# DIGISPARK_PRODUCTION_REV3.net
KiCad netlist of a schematic drawn in EAGLE
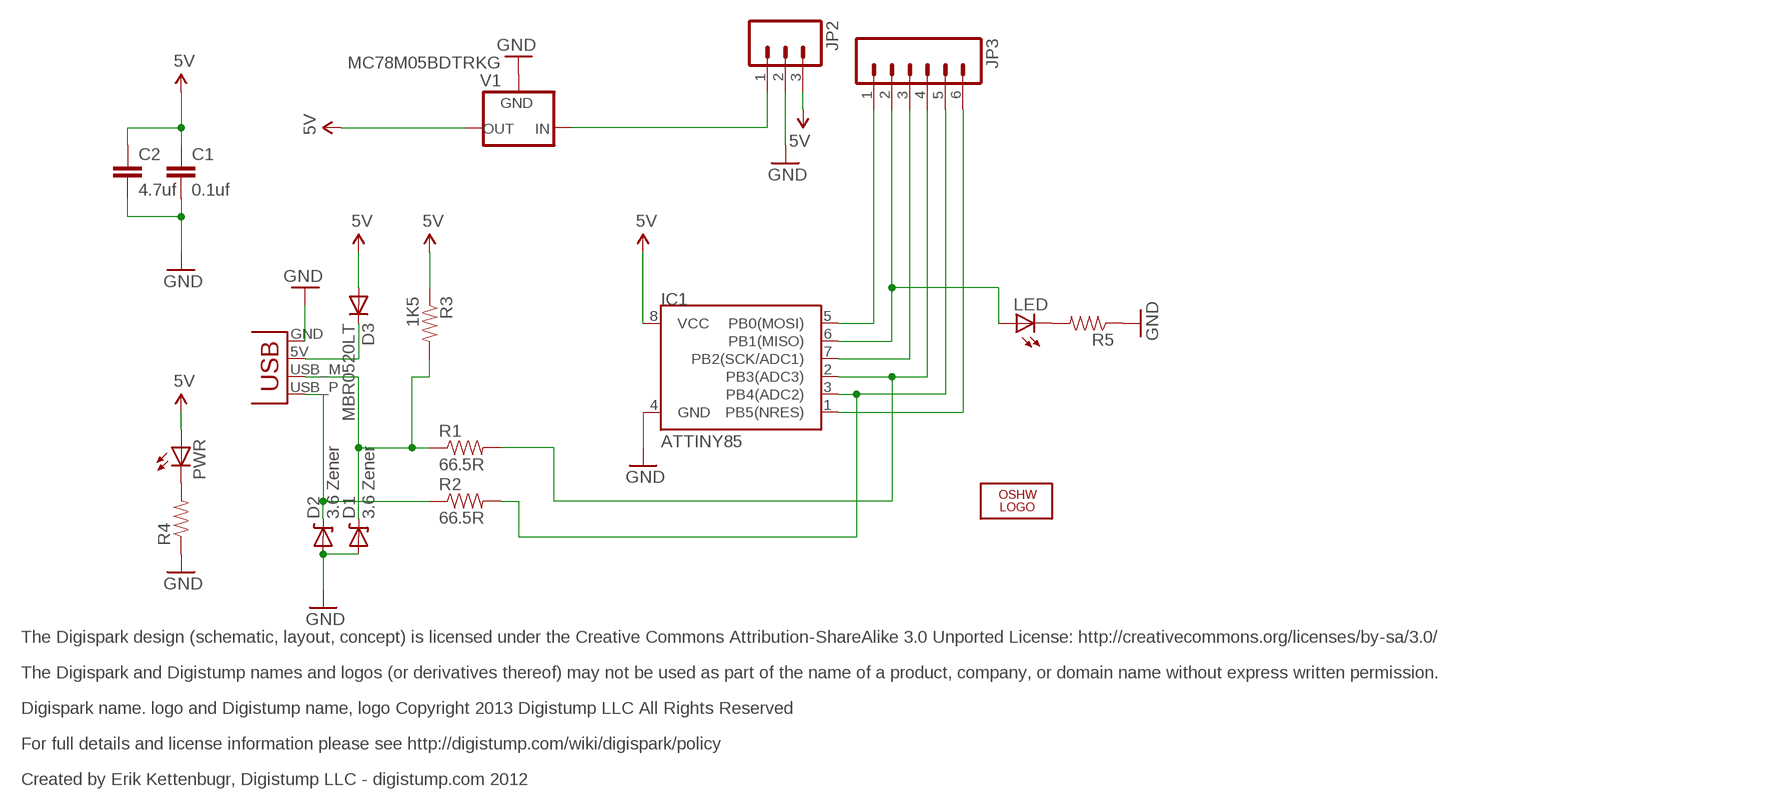
[diagram p0: schematic, sheet 1]

(export (version "E")
  (design (tool "Eeschema 10.0.6"))
  (components
    (comp (ref "C1")
      (value "0.1uf")
      (footprint "eagle-import:0402-CAP")
      (libsource (lib "eagle-import") (part "CAP0402-CAP"))
    )
    (comp (ref "C2")
      (value "4.7uf")
      (footprint "eagle-import:0805")
      (libsource (lib "eagle-import") (part "CAP0805"))
    )
    (comp (ref "D1")
      (value "3.6 Zener")
      (footprint "eagle-import:SOD-323")
      (libsource (lib "eagle-import") (part "DIODE-ZENER-BZT52"))
    )
    (comp (ref "D2")
      (value "3.6 Zener")
      (footprint "eagle-import:SOD-323")
      (libsource (lib "eagle-import") (part "DIODE-ZENER-BZT52"))
    )
    (comp (ref "D3")
      (value "MBR0520LT")
      (footprint "eagle-import:SOD123")
      (libsource (lib "eagle-import") (part "MBR0520LT"))
    )
    (comp (ref "IC1")
      (value "ATTINY85")
      (footprint "eagle-import:SO08-EIAJ")
      (libsource (lib "eagle-import") (part "ATTINY45"))
    )
    (comp (ref "JP2")
      (value "M03PTH")
      (footprint "eagle-import:1X03")
      (libsource (lib "eagle-import") (part "M03PTH"))
    )
    (comp (ref "JP3")
      (value "M06SIP")
      (footprint "eagle-import:1X06")
      (libsource (lib "eagle-import") (part "M06SIP"))
    )
    (comp (ref "LED")
      (value "LED0603")
      (footprint "eagle-import:LED-0603")
      (libsource (lib "eagle-import") (part "LED0603"))
    )
    (comp (ref "LOGO2")
      (value "LOGO-OSHW-10MILX0200-NT")
      (footprint "eagle-import:OSHW_10X200_NOTEXT")
      (libsource (lib "eagle-import") (part "LOGO-OSHW-10MILX0200-NT"))
    )
    (comp (ref "PWR")
      (value "LED0603")
      (footprint "eagle-import:LED-0603")
      (libsource (lib "eagle-import") (part "LED0603"))
    )
    (comp (ref "R1")
      (value "66.5R")
      (footprint "eagle-import:0402-RES")
      (libsource (lib "eagle-import") (part "RESISTOR0402-RES"))
    )
    (comp (ref "R2")
      (value "66.5R")
      (footprint "eagle-import:0402-RES")
      (libsource (lib "eagle-import") (part "RESISTOR0402-RES"))
    )
    (comp (ref "R3")
      (value "1K5")
      (footprint "eagle-import:0402-RES")
      (libsource (lib "eagle-import") (part "RESISTOR0402-RES"))
    )
    (comp (ref "R4")
      (value "RESISTOR0402-RES")
      (footprint "eagle-import:0402-RES")
      (libsource (lib "eagle-import") (part "RESISTOR0402-RES"))
    )
    (comp (ref "R5")
      (value "RESISTOR0402-RES")
      (footprint "eagle-import:0402-RES")
      (libsource (lib "eagle-import") (part "RESISTOR0402-RES"))
    )
    (comp (ref "V1")
      (value "MC78M05BDTRKG")
      (footprint "eagle-import:DPACK")
      (libsource (lib "eagle-import") (part "LP2950?CDT-3.0"))
    )
    (comp (ref "X1")
      (value "USBPCB")
      (footprint "eagle-import:USB-A-PCB")
      (libsource (lib "eagle-import") (part "USBPCB"))
    )
  )
  (nets
    (net (code "1") (name "5V") (class "Default")
      (node (ref "C1") (pin "1") (pinfunction "1_1") (pintype "passive"))
      (node (ref "C2") (pin "1") (pinfunction "1_1") (pintype "passive"))
      (node (ref "D3") (pin "A") (pinfunction "A_A") (pintype "passive"))
      (node (ref "IC1") (pin "8") (pinfunction "VCC_8") (pintype "bidirectional"))
      (node (ref "JP2") (pin "3") (pinfunction "3_3") (pintype "passive"))
      (node (ref "PWR") (pin "A") (pinfunction "A_A") (pintype "passive"))
      (node (ref "R3") (pin "1") (pinfunction "1_1") (pintype "passive"))
      (node (ref "V1") (pin "3") (pinfunction "OUT_3") (pintype "passive"))
    )
    (net (code "2") (name "GND") (class "Default")
      (node (ref "C1") (pin "2") (pinfunction "2_2") (pintype "passive"))
      (node (ref "C2") (pin "2") (pinfunction "2_2") (pintype "passive"))
      (node (ref "D1") (pin "2") (pinfunction "A_2") (pintype "passive"))
      (node (ref "D2") (pin "2") (pinfunction "A_2") (pintype "passive"))
      (node (ref "IC1") (pin "4") (pinfunction "GND_4") (pintype "bidirectional"))
      (node (ref "JP2") (pin "2") (pinfunction "2_2") (pintype "passive"))
      (node (ref "R4") (pin "1") (pinfunction "1_1") (pintype "passive"))
      (node (ref "R5") (pin "1") (pinfunction "1_1") (pintype "passive"))
      (node (ref "V1") (pin "4") (pinfunction "GND_4") (pintype "input"))
      (node (ref "X1") (pin "GND") (pinfunction "GND_GND") (pintype "bidirectional"))
    )
    (net (code "3") (name "Net-(D1-C)") (class "Default")
      (node (ref "D1") (pin "1") (pinfunction "C_1") (pintype "passive"))
      (node (ref "R1") (pin "1") (pinfunction "1_1") (pintype "passive"))
      (node (ref "R3") (pin "2") (pinfunction "2_2") (pintype "passive"))
      (node (ref "X1") (pin "USB_M") (pinfunction "D-_USB_M") (pintype "bidirectional"))
    )
    (net (code "4") (name "Net-(D2-C)") (class "Default")
      (node (ref "D2") (pin "1") (pinfunction "C_1") (pintype "passive"))
      (node (ref "R2") (pin "1") (pinfunction "1_1") (pintype "passive"))
      (node (ref "X1") (pin "USB_P") (pinfunction "D+_USB_P") (pintype "bidirectional"))
    )
    (net (code "5") (name "Net-(IC1-PB0(MOSI))") (class "Default")
      (node (ref "IC1") (pin "5") (pinfunction "PB0(MOSI)_5") (pintype "bidirectional"))
      (node (ref "JP3") (pin "1") (pinfunction "1_1") (pintype "passive"))
    )
    (net (code "6") (name "Net-(IC1-PB1(MISO))") (class "Default")
      (node (ref "IC1") (pin "6") (pinfunction "PB1(MISO)_6") (pintype "bidirectional"))
      (node (ref "JP3") (pin "2") (pinfunction "2_2") (pintype "passive"))
      (node (ref "LED") (pin "A") (pinfunction "A_A") (pintype "passive"))
    )
    (net (code "7") (name "Net-(IC1-PB2(SCK{slash}ADC1))") (class "Default")
      (node (ref "IC1") (pin "7") (pinfunction "PB2(SCK/ADC1)_7") (pintype "bidirectional"))
      (node (ref "JP3") (pin "3") (pinfunction "3_3") (pintype "passive"))
    )
    (net (code "8") (name "Net-(IC1-PB3(ADC3))") (class "Default")
      (node (ref "IC1") (pin "2") (pinfunction "PB3(ADC3)_2") (pintype "bidirectional"))
      (node (ref "JP3") (pin "4") (pinfunction "4_4") (pintype "passive"))
      (node (ref "R1") (pin "2") (pinfunction "2_2") (pintype "passive"))
    )
    (net (code "9") (name "Net-(IC1-PB4(ADC2))") (class "Default")
      (node (ref "IC1") (pin "3") (pinfunction "PB4(ADC2)_3") (pintype "bidirectional"))
      (node (ref "JP3") (pin "5") (pinfunction "5_5") (pintype "passive"))
      (node (ref "R2") (pin "2") (pinfunction "2_2") (pintype "passive"))
    )
    (net (code "10") (name "Net-(IC1-PB5(NRES))") (class "Default")
      (node (ref "IC1") (pin "1") (pinfunction "PB5(NRES)_1") (pintype "bidirectional"))
      (node (ref "JP3") (pin "6") (pinfunction "6_6") (pintype "passive"))
    )
    (net (code "11") (name "Net-(LED-PadC)") (class "Default")
      (node (ref "LED") (pin "C") (pinfunction "C_C") (pintype "passive"))
      (node (ref "R5") (pin "2") (pinfunction "2_2") (pintype "passive"))
    )
    (net (code "12") (name "Net-(PWR-PadC)") (class "Default")
      (node (ref "PWR") (pin "C") (pinfunction "C_C") (pintype "passive"))
      (node (ref "R4") (pin "2") (pinfunction "2_2") (pintype "passive"))
    )
    (net (code "13") (name "Net-(V1-IN)") (class "Default")
      (node (ref "JP2") (pin "1") (pinfunction "1_1") (pintype "passive"))
      (node (ref "V1") (pin "1") (pinfunction "IN_1") (pintype "input"))
    )
    (net (code "14") (name "Net-(X1-VBUS)") (class "Default")
      (node (ref "D3") (pin "C") (pinfunction "C_C") (pintype "passive"))
      (node (ref "X1") (pin "5V") (pinfunction "VBUS_5V") (pintype "bidirectional"))
    )
  )
)
